# cubex_power.net
KiCad netlist of a schematic drawn in EAGLE
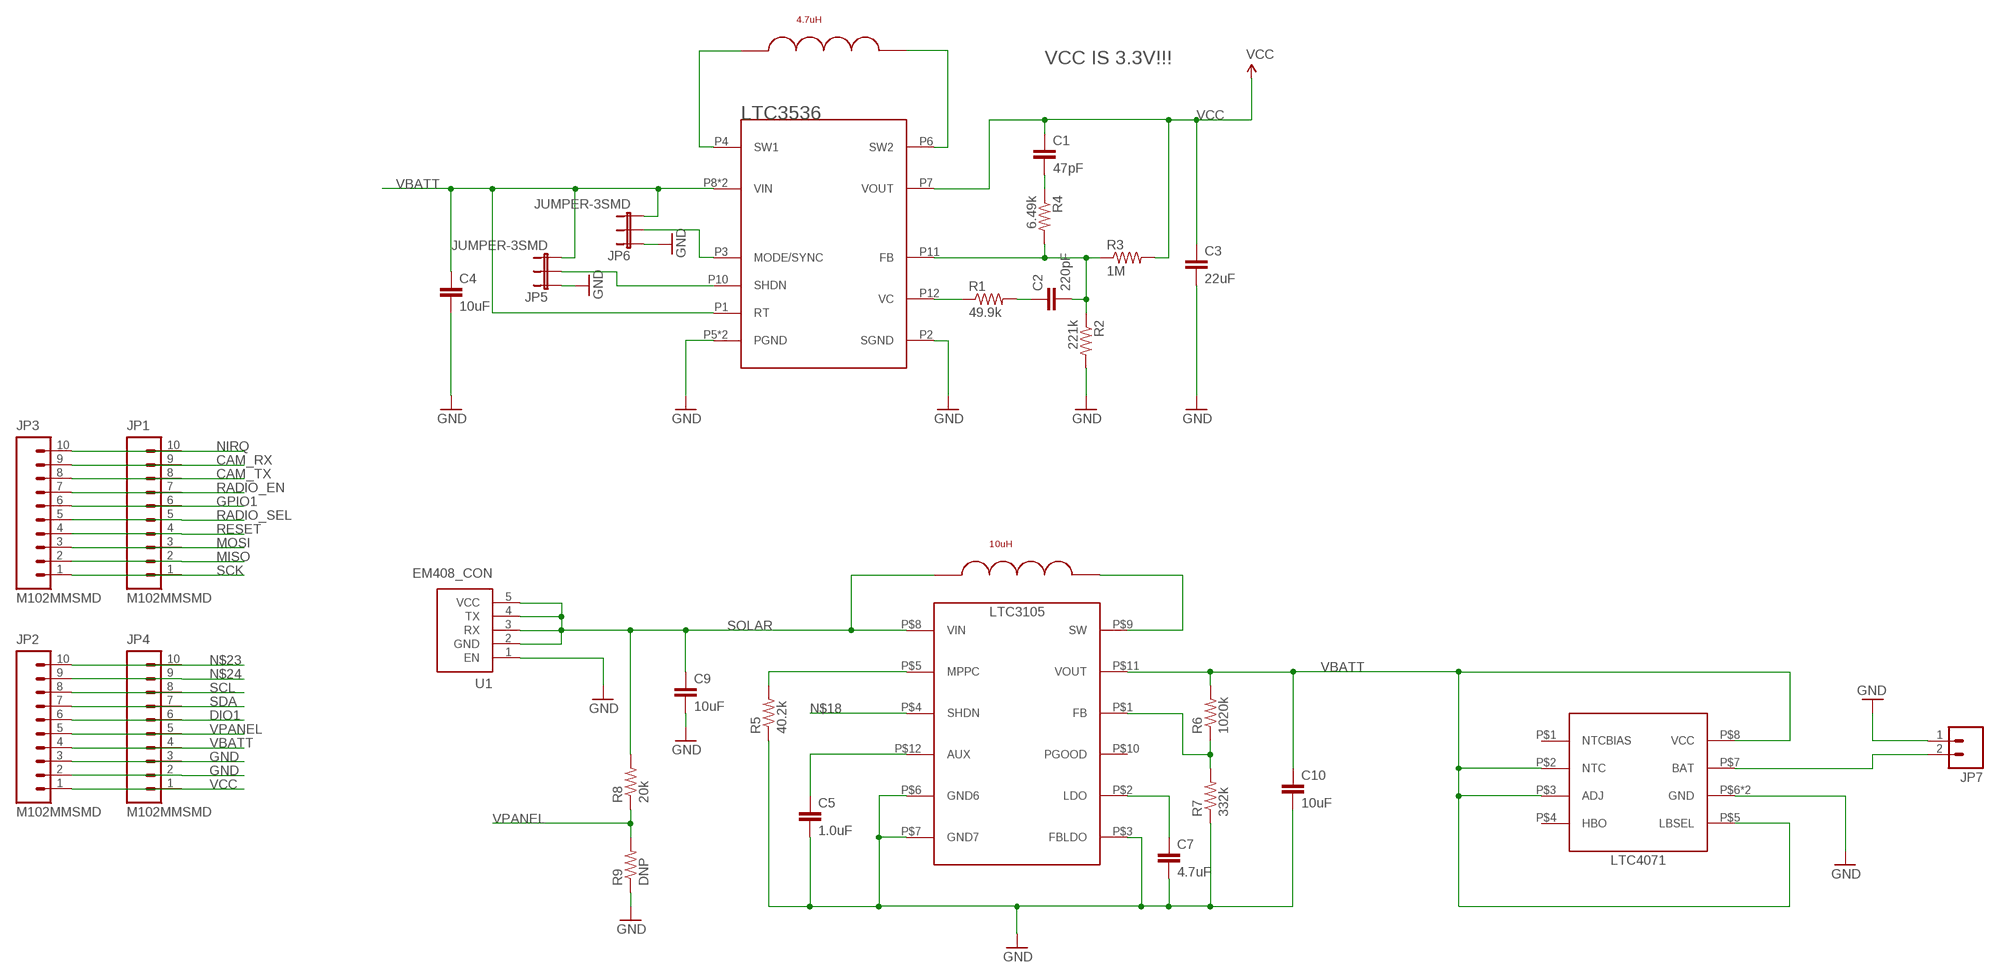
[diagram p0: schematic, sheet 1]

(export (version "E")
  (design (tool "Eeschema 10.0.6"))
  (components
    (comp (ref "C1")
      (value "47pF")
      (footprint "eagle-import:1206")
      (libsource (lib "eagle-import") (part "CAP1206"))
    )
    (comp (ref "C2")
      (value "220pF")
      (footprint "eagle-import:1206")
      (libsource (lib "eagle-import") (part "CAP1206"))
    )
    (comp (ref "C3")
      (value "22uF")
      (footprint "eagle-import:1206")
      (libsource (lib "eagle-import") (part "CAP1206"))
    )
    (comp (ref "C4")
      (value "10uF")
      (footprint "eagle-import:1206")
      (libsource (lib "eagle-import") (part "CAP1206"))
    )
    (comp (ref "C5")
      (value "1.0uF")
      (footprint "eagle-import:0805")
      (libsource (lib "eagle-import") (part "1.0UF-25V-+80/-20(0805)"))
    )
    (comp (ref "C7")
      (value "4.7uF")
      (footprint "eagle-import:0805")
      (libsource (lib "eagle-import") (part "SparkFun-Capacitors_CAP0805"))
    )
    (comp (ref "C9")
      (value "10uF")
      (footprint "eagle-import:1206")
      (libsource (lib "eagle-import") (part "SparkFun-Capacitors_CAP1206"))
    )
    (comp (ref "C10")
      (value "10uF")
      (footprint "eagle-import:1206")
      (libsource (lib "eagle-import") (part "SparkFun-Capacitors_CAP1206"))
    )
    (comp (ref "JP1")
      (value "M102MMSMD")
      (footprint "eagle-import:1X10-2MM-SMD")
      (libsource (lib "eagle-import") (part "M102MMSMD"))
    )
    (comp (ref "JP2")
      (value "M102MMSMD")
      (footprint "eagle-import:1X10-2MM-SMD")
      (libsource (lib "eagle-import") (part "M102MMSMD"))
    )
    (comp (ref "JP3")
      (value "M102MMSMD")
      (footprint "eagle-import:1X10-2MM-SMD")
      (libsource (lib "eagle-import") (part "M102MMSMD"))
    )
    (comp (ref "JP4")
      (value "M102MMSMD")
      (footprint "eagle-import:1X10-2MM-SMD")
      (libsource (lib "eagle-import") (part "M102MMSMD"))
    )
    (comp (ref "JP5")
      (value "JUMPER-3SMD")
      (footprint "eagle-import:SJ_3")
      (libsource (lib "eagle-import") (part "JUMPER-3SMD"))
    )
    (comp (ref "JP6")
      (value "JUMPER-3SMD")
      (footprint "eagle-import:SJ_3")
      (libsource (lib "eagle-import") (part "JUMPER-3SMD"))
    )
    (comp (ref "JP7")
      (value "M02JST-PTH-2")
      (footprint "eagle-import:JST-2-PTH")
      (libsource (lib "eagle-import") (part "M02JST-PTH-2"))
    )
    (comp (ref "R1")
      (value "49.9k")
      (footprint "eagle-import:1206")
      (libsource (lib "eagle-import") (part "RESISTOR1206"))
    )
    (comp (ref "R2")
      (value "221k")
      (footprint "eagle-import:1206")
      (libsource (lib "eagle-import") (part "RESISTOR1206"))
    )
    (comp (ref "R3")
      (value "1M")
      (footprint "eagle-import:1206")
      (libsource (lib "eagle-import") (part "RESISTOR1206"))
    )
    (comp (ref "R4")
      (value "6.49k")
      (footprint "eagle-import:1206")
      (libsource (lib "eagle-import") (part "RESISTOR1206"))
    )
    (comp (ref "R5")
      (value "40.2k")
      (footprint "eagle-import:0805")
      (libsource (lib "eagle-import") (part "SparkFun-Resistors_RESISTOR0805-RES"))
    )
    (comp (ref "R6")
      (value "1020k")
      (footprint "eagle-import:0805")
      (libsource (lib "eagle-import") (part "SparkFun-Resistors_RESISTOR0805-RES"))
    )
    (comp (ref "R7")
      (value "332k")
      (footprint "eagle-import:0805")
      (libsource (lib "eagle-import") (part "SparkFun-Resistors_RESISTOR0805-RES"))
    )
    (comp (ref "R8")
      (value "20k")
      (footprint "eagle-import:0805")
      (libsource (lib "eagle-import") (part "SparkFun-Resistors_RESISTOR0805-RES"))
    )
    (comp (ref "R9")
      (value "DNP")
      (footprint "eagle-import:0805")
      (libsource (lib "eagle-import") (part "SparkFun-Resistors_RESISTOR0805-RES"))
    )
    (comp (ref "U$1")
      (value "LTC3105")
      (footprint "eagle-import:LTC3105")
      (libsource (lib "eagle-import") (part "LTC3105"))
    )
    (comp (ref "U$2")
      (value "4.7uH")
      (footprint "eagle-import:STEVESCOILCRAFT_COILCRAFT_LPS4018")
      (libsource (lib "eagle-import") (part "STEVESCOILCRAFT_COILCRAFT_LPS4018"))
    )
    (comp (ref "U$3")
      (value "LTC3536")
      (footprint "eagle-import:LTC3536-MSE")
      (libsource (lib "eagle-import") (part "LTC3536"))
    )
    (comp (ref "U$4")
      (value "10uH")
      (footprint "eagle-import:STEVESCOILCRAFT_COILCRAFT_LPS4018")
      (libsource (lib "eagle-import") (part "STEVESCOILCRAFT_COILCRAFT_LPS4018"))
    )
    (comp (ref "U$5")
      (value "LTC4071")
      (footprint "eagle-import:LTC4071")
      (libsource (lib "eagle-import") (part "LTC4071"))
    )
    (comp (ref "U1")
      (value "EM408_CON")
      (footprint "eagle-import:EM408_CON")
      (libsource (lib "eagle-import") (part "EM408_CON"))
    )
  )
  (nets
    (net (code "1") (name "/CAM_RX") (class "Default")
      (node (ref "JP1") (pin "9") (pinfunction "9_9") (pintype "passive"))
      (node (ref "JP3") (pin "9") (pinfunction "9_9") (pintype "passive"))
    )
    (net (code "2") (name "/CAM_TX") (class "Default")
      (node (ref "JP1") (pin "8") (pinfunction "8_8") (pintype "passive"))
      (node (ref "JP3") (pin "8") (pinfunction "8_8") (pintype "passive"))
    )
    (net (code "3") (name "/DIO1") (class "Default")
      (node (ref "JP2") (pin "6") (pinfunction "6_6") (pintype "passive"))
      (node (ref "JP4") (pin "6") (pinfunction "6_6") (pintype "passive"))
    )
    (net (code "4") (name "/GPIO1") (class "Default")
      (node (ref "JP1") (pin "6") (pinfunction "6_6") (pintype "passive"))
      (node (ref "JP3") (pin "6") (pinfunction "6_6") (pintype "passive"))
    )
    (net (code "5") (name "/MISO") (class "Default")
      (node (ref "JP1") (pin "2") (pinfunction "2_2") (pintype "passive"))
      (node (ref "JP3") (pin "2") (pinfunction "2_2") (pintype "passive"))
    )
    (net (code "6") (name "/MOSI") (class "Default")
      (node (ref "JP1") (pin "3") (pinfunction "3_3") (pintype "passive"))
      (node (ref "JP3") (pin "3") (pinfunction "3_3") (pintype "passive"))
    )
    (net (code "7") (name "/N$18") (class "Default")
      (node (ref "U$1") (pin "P$4") (pinfunction "SHDN_P$4") (pintype "bidirectional"))
    )
    (net (code "8") (name "/N$23") (class "Default")
      (node (ref "JP2") (pin "10") (pinfunction "10_10") (pintype "passive"))
      (node (ref "JP4") (pin "10") (pinfunction "10_10") (pintype "passive"))
    )
    (net (code "9") (name "/N$24") (class "Default")
      (node (ref "JP2") (pin "9") (pinfunction "9_9") (pintype "passive"))
      (node (ref "JP4") (pin "9") (pinfunction "9_9") (pintype "passive"))
    )
    (net (code "10") (name "/NIRQ") (class "Default")
      (node (ref "JP1") (pin "10") (pinfunction "10_10") (pintype "passive"))
      (node (ref "JP3") (pin "10") (pinfunction "10_10") (pintype "passive"))
    )
    (net (code "11") (name "/RADIO_EN") (class "Default")
      (node (ref "JP1") (pin "7") (pinfunction "7_7") (pintype "passive"))
      (node (ref "JP3") (pin "7") (pinfunction "7_7") (pintype "passive"))
    )
    (net (code "12") (name "/RADIO_SEL") (class "Default")
      (node (ref "JP1") (pin "5") (pinfunction "5_5") (pintype "passive"))
      (node (ref "JP3") (pin "5") (pinfunction "5_5") (pintype "passive"))
    )
    (net (code "13") (name "/RESET") (class "Default")
      (node (ref "JP1") (pin "4") (pinfunction "4_4") (pintype "passive"))
      (node (ref "JP3") (pin "4") (pinfunction "4_4") (pintype "passive"))
    )
    (net (code "14") (name "/SCK") (class "Default")
      (node (ref "JP1") (pin "1") (pinfunction "1_1") (pintype "passive"))
      (node (ref "JP3") (pin "1") (pinfunction "1_1") (pintype "passive"))
    )
    (net (code "15") (name "/SCL") (class "Default")
      (node (ref "JP2") (pin "8") (pinfunction "8_8") (pintype "passive"))
      (node (ref "JP4") (pin "8") (pinfunction "8_8") (pintype "passive"))
    )
    (net (code "16") (name "/SDA") (class "Default")
      (node (ref "JP2") (pin "7") (pinfunction "7_7") (pintype "passive"))
      (node (ref "JP4") (pin "7") (pinfunction "7_7") (pintype "passive"))
    )
    (net (code "17") (name "/SOLAR") (class "Default")
      (node (ref "C9") (pin "1") (pinfunction "1_1") (pintype "passive"))
      (node (ref "R8") (pin "2") (pinfunction "2_2") (pintype "passive"))
      (node (ref "U$1") (pin "P$8") (pinfunction "VIN_P$8") (pintype "bidirectional"))
      (node (ref "U$4") (pin "P$1") (pinfunction "P$1_P$1") (pintype "bidirectional"))
      (node (ref "U1") (pin "2") (pinfunction "GND_2") (pintype "bidirectional"))
      (node (ref "U1") (pin "3") (pinfunction "RX_3") (pintype "bidirectional"))
      (node (ref "U1") (pin "4") (pinfunction "TX_4") (pintype "bidirectional"))
      (node (ref "U1") (pin "5") (pinfunction "VCC_5") (pintype "bidirectional"))
    )
    (net (code "18") (name "/VBATT") (class "Default")
      (node (ref "C10") (pin "1") (pinfunction "1_1") (pintype "passive"))
      (node (ref "C4") (pin "1") (pinfunction "1_1") (pintype "passive"))
      (node (ref "JP2") (pin "4") (pinfunction "4_4") (pintype "passive"))
      (node (ref "JP4") (pin "4") (pinfunction "4_4") (pintype "passive"))
      (node (ref "JP5") (pin "3") (pinfunction "3_3") (pintype "passive"))
      (node (ref "JP6") (pin "3") (pinfunction "3_3") (pintype "passive"))
      (node (ref "R6") (pin "2") (pinfunction "2_2") (pintype "passive"))
      (node (ref "U$1") (pin "P$11") (pinfunction "VOUT_P$11") (pintype "bidirectional"))
      (node (ref "U$3") (pin "P1") (pinfunction "RT_P1") (pintype "bidirectional"))
      (node (ref "U$3") (pin "P8") (pinfunction "VIN_P8") (pintype "bidirectional"))
      (node (ref "U$3") (pin "P9") (pinfunction "VIN_P9") (pintype "bidirectional"))
      (node (ref "U$5") (pin "P$2") (pinfunction "NTC_P$2") (pintype "bidirectional"))
      (node (ref "U$5") (pin "P$3") (pinfunction "ADJ_P$3") (pintype "bidirectional"))
      (node (ref "U$5") (pin "P$5") (pinfunction "LBSEL_P$5") (pintype "bidirectional"))
      (node (ref "U$5") (pin "P$8") (pinfunction "VCC_P$8") (pintype "bidirectional"))
    )
    (net (code "19") (name "/VPANEL") (class "Default")
      (node (ref "JP2") (pin "5") (pinfunction "5_5") (pintype "passive"))
      (node (ref "JP4") (pin "5") (pinfunction "5_5") (pintype "passive"))
      (node (ref "R8") (pin "1") (pinfunction "1_1") (pintype "passive"))
      (node (ref "R9") (pin "2") (pinfunction "2_2") (pintype "passive"))
    )
    (net (code "20") (name "GND") (class "Default")
      (node (ref "C10") (pin "2") (pinfunction "2_2") (pintype "passive"))
      (node (ref "C3") (pin "2") (pinfunction "2_2") (pintype "passive"))
      (node (ref "C4") (pin "2") (pinfunction "2_2") (pintype "passive"))
      (node (ref "C5") (pin "2") (pinfunction "2_2") (pintype "passive"))
      (node (ref "C7") (pin "2") (pinfunction "2_2") (pintype "passive"))
      (node (ref "C9") (pin "2") (pinfunction "2_2") (pintype "passive"))
      (node (ref "JP2") (pin "2") (pinfunction "2_2") (pintype "passive"))
      (node (ref "JP2") (pin "3") (pinfunction "3_3") (pintype "passive"))
      (node (ref "JP4") (pin "2") (pinfunction "2_2") (pintype "passive"))
      (node (ref "JP4") (pin "3") (pinfunction "3_3") (pintype "passive"))
      (node (ref "JP5") (pin "1") (pinfunction "1_1") (pintype "passive"))
      (node (ref "JP6") (pin "1") (pinfunction "1_1") (pintype "passive"))
      (node (ref "JP7") (pin "1") (pinfunction "1_1") (pintype "passive"))
      (node (ref "R2") (pin "2") (pinfunction "2_2") (pintype "passive"))
      (node (ref "R5") (pin "1") (pinfunction "1_1") (pintype "passive"))
      (node (ref "R7") (pin "1") (pinfunction "1_1") (pintype "passive"))
      (node (ref "R9") (pin "1") (pinfunction "1_1") (pintype "passive"))
      (node (ref "U$1") (pin "P$3") (pinfunction "FBLDO_P$3") (pintype "bidirectional"))
      (node (ref "U$1") (pin "P$6") (pinfunction "GND6_P$6") (pintype "bidirectional"))
      (node (ref "U$1") (pin "P$7") (pinfunction "GND7_P$7") (pintype "bidirectional"))
      (node (ref "U$3") (pin "P13") (pinfunction "PGND_P13") (pintype "bidirectional"))
      (node (ref "U$3") (pin "P2") (pinfunction "SGND_P2") (pintype "bidirectional"))
      (node (ref "U$3") (pin "P5") (pinfunction "PGND_P5") (pintype "bidirectional"))
      (node (ref "U$5") (pin "P$6") (pinfunction "GND_P$6") (pintype "bidirectional"))
      (node (ref "U$5") (pin "P$9") (pinfunction "GND_P$9") (pintype "bidirectional"))
      (node (ref "U1") (pin "1") (pinfunction "EN_1") (pintype "bidirectional"))
    )
    (net (code "21") (name "Net-(C1-Pad2)") (class "Default")
      (node (ref "C1") (pin "2") (pinfunction "2_2") (pintype "passive"))
      (node (ref "R4") (pin "1") (pinfunction "1_1") (pintype "passive"))
    )
    (net (code "22") (name "Net-(C2-Pad1)") (class "Default")
      (node (ref "C2") (pin "1") (pinfunction "1_1") (pintype "passive"))
      (node (ref "R1") (pin "2") (pinfunction "2_2") (pintype "passive"))
    )
    (net (code "23") (name "Net-(U$1-AUX)") (class "Default")
      (node (ref "C5") (pin "1") (pinfunction "1_1") (pintype "passive"))
      (node (ref "U$1") (pin "P$12") (pinfunction "AUX_P$12") (pintype "bidirectional"))
    )
    (net (code "24") (name "Net-(U$1-FB)") (class "Default")
      (node (ref "R6") (pin "1") (pinfunction "1_1") (pintype "passive"))
      (node (ref "R7") (pin "2") (pinfunction "2_2") (pintype "passive"))
      (node (ref "U$1") (pin "P$1") (pinfunction "FB_P$1") (pintype "bidirectional"))
    )
    (net (code "25") (name "Net-(U$1-LDO)") (class "Default")
      (node (ref "C7") (pin "1") (pinfunction "1_1") (pintype "passive"))
      (node (ref "U$1") (pin "P$2") (pinfunction "LDO_P$2") (pintype "bidirectional"))
    )
    (net (code "26") (name "Net-(U$1-MPPC)") (class "Default")
      (node (ref "R5") (pin "2") (pinfunction "2_2") (pintype "passive"))
      (node (ref "U$1") (pin "P$5") (pinfunction "MPPC_P$5") (pintype "bidirectional"))
    )
    (net (code "27") (name "Net-(U$1-SW)") (class "Default")
      (node (ref "U$1") (pin "P$9") (pinfunction "SW_P$9") (pintype "bidirectional"))
      (node (ref "U$4") (pin "P$2") (pinfunction "P$2_P$2") (pintype "bidirectional"))
    )
    (net (code "28") (name "Net-(U$3-FB)") (class "Default")
      (node (ref "C2") (pin "2") (pinfunction "2_2") (pintype "passive"))
      (node (ref "R2") (pin "1") (pinfunction "1_1") (pintype "passive"))
      (node (ref "R3") (pin "1") (pinfunction "1_1") (pintype "passive"))
      (node (ref "R4") (pin "2") (pinfunction "2_2") (pintype "passive"))
      (node (ref "U$3") (pin "P11") (pinfunction "FB_P11") (pintype "bidirectional"))
    )
    (net (code "29") (name "Net-(U$3-MODE{slash}SYNC)") (class "Default")
      (node (ref "JP6") (pin "2") (pinfunction "2_2") (pintype "passive"))
      (node (ref "U$3") (pin "P3") (pinfunction "MODE/SYNC_P3") (pintype "bidirectional"))
    )
    (net (code "30") (name "Net-(U$3-SHDN)") (class "Default")
      (node (ref "JP5") (pin "2") (pinfunction "2_2") (pintype "passive"))
      (node (ref "U$3") (pin "P10") (pinfunction "SHDN_P10") (pintype "bidirectional"))
    )
    (net (code "31") (name "Net-(U$3-SW1)") (class "Default")
      (node (ref "U$2") (pin "P$1") (pinfunction "P$1_P$1") (pintype "bidirectional"))
      (node (ref "U$3") (pin "P4") (pinfunction "SW1_P4") (pintype "bidirectional"))
    )
    (net (code "32") (name "Net-(U$3-SW2)") (class "Default")
      (node (ref "U$2") (pin "P$2") (pinfunction "P$2_P$2") (pintype "bidirectional"))
      (node (ref "U$3") (pin "P6") (pinfunction "SW2_P6") (pintype "bidirectional"))
    )
    (net (code "33") (name "Net-(U$3-VC)") (class "Default")
      (node (ref "R1") (pin "1") (pinfunction "1_1") (pintype "passive"))
      (node (ref "U$3") (pin "P12") (pinfunction "VC_P12") (pintype "bidirectional"))
    )
    (net (code "34") (name "Net-(U$5-BAT)") (class "Default")
      (node (ref "JP7") (pin "2") (pinfunction "2_2") (pintype "passive"))
      (node (ref "U$5") (pin "P$7") (pinfunction "BAT_P$7") (pintype "bidirectional"))
    )
    (net (code "35") (name "VCC") (class "Default")
      (node (ref "C1") (pin "1") (pinfunction "1_1") (pintype "passive"))
      (node (ref "C3") (pin "1") (pinfunction "1_1") (pintype "passive"))
      (node (ref "JP2") (pin "1") (pinfunction "1_1") (pintype "passive"))
      (node (ref "JP4") (pin "1") (pinfunction "1_1") (pintype "passive"))
      (node (ref "R3") (pin "2") (pinfunction "2_2") (pintype "passive"))
      (node (ref "U$3") (pin "P7") (pinfunction "VOUT_P7") (pintype "bidirectional"))
    )
    (net (code "36") (name "unconnected-(U$1-PGOOD-PadP$10)") (class "Default")
      (node (ref "U$1") (pin "P$10") (pinfunction "PGOOD_P$10") (pintype "bidirectional"))
    )
    (net (code "37") (name "unconnected-(U$5-HBO-PadP$4)") (class "Default")
      (node (ref "U$5") (pin "P$4") (pinfunction "HBO_P$4") (pintype "bidirectional"))
    )
    (net (code "38") (name "unconnected-(U$5-NTCBIAS-PadP$1)") (class "Default")
      (node (ref "U$5") (pin "P$1") (pinfunction "NTCBIAS_P$1") (pintype "bidirectional"))
    )
  )
)
